# schematic.net
KiCad netlist of a schematic drawn in Altium Designer
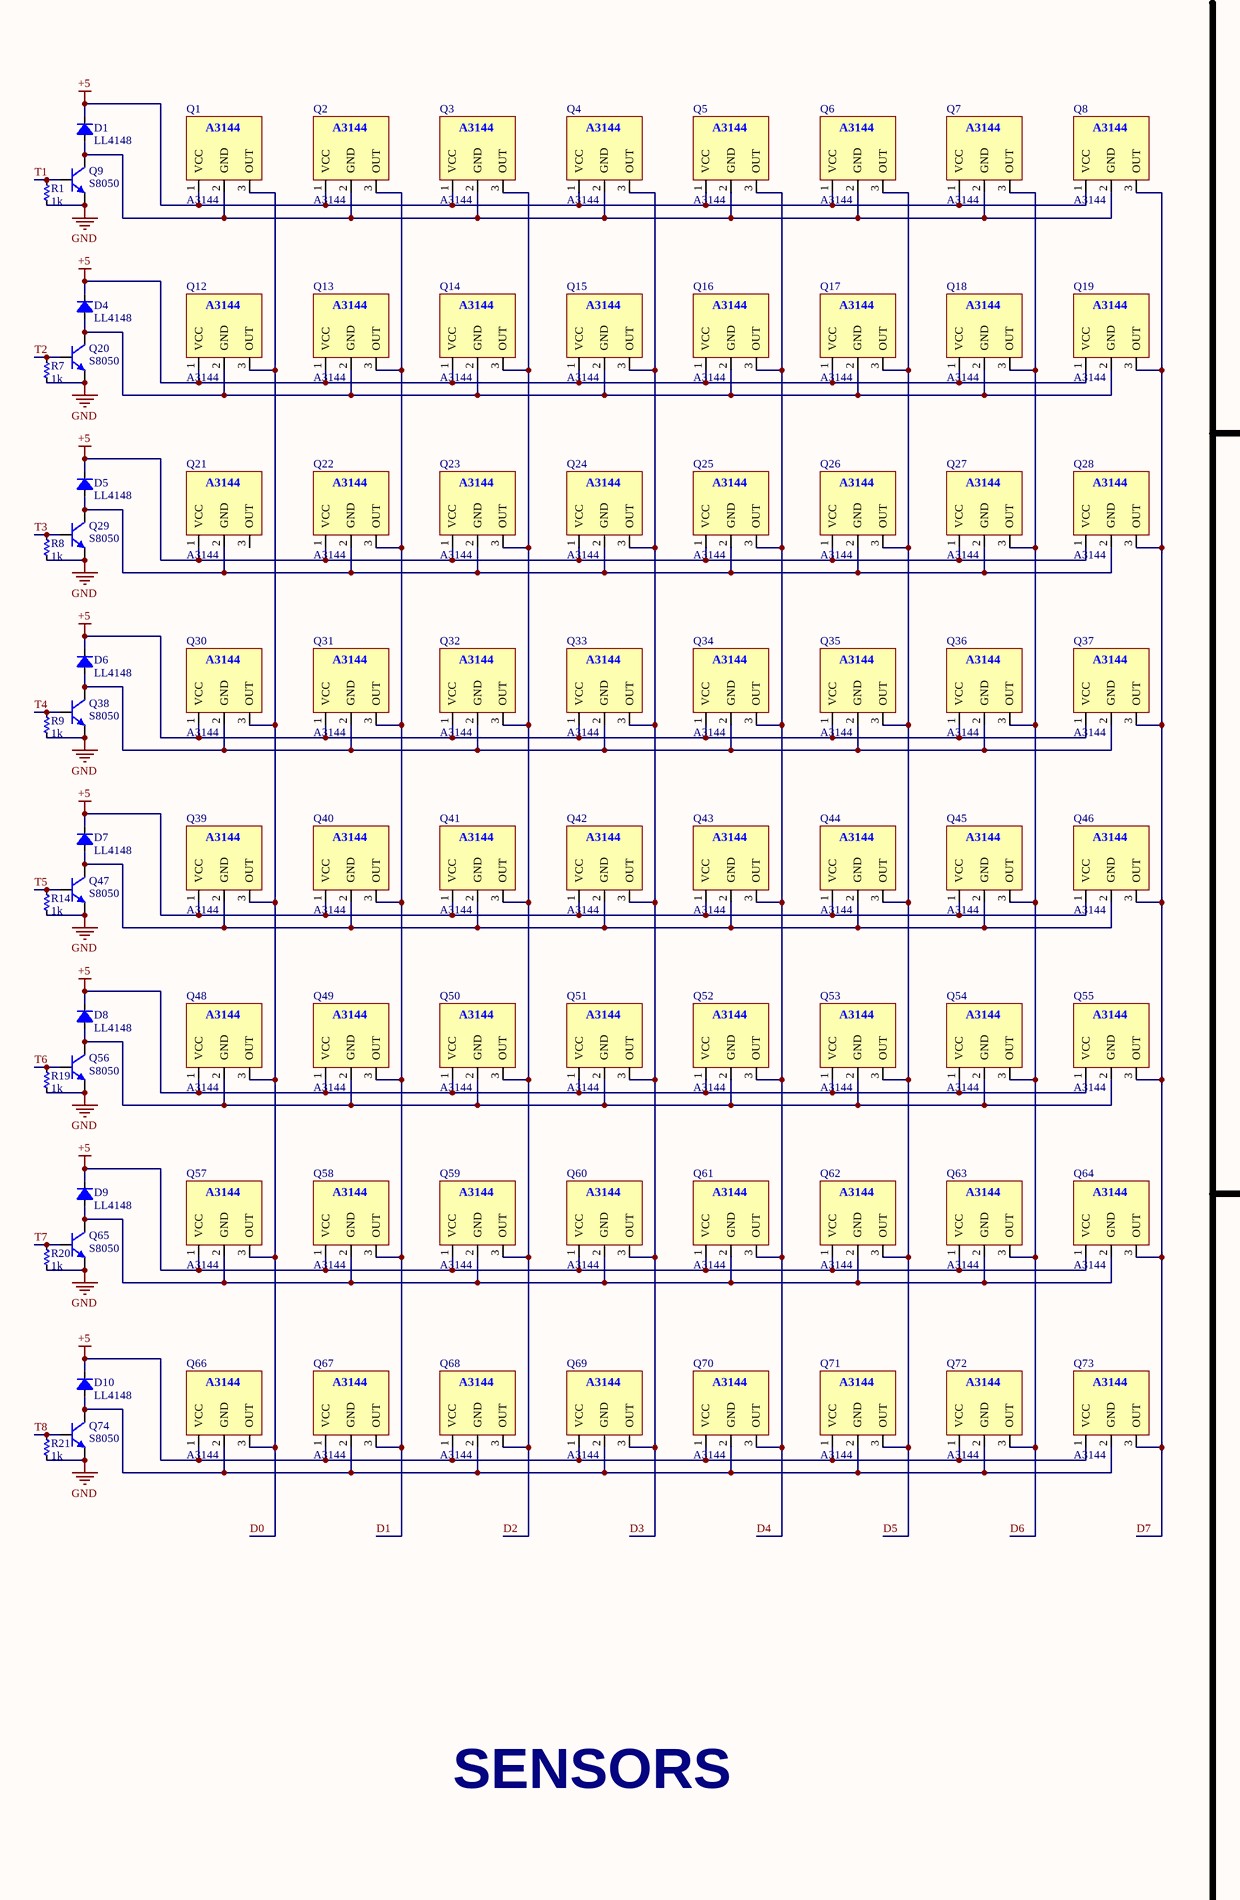
[diagram p0: schematic.SchDoc, left]
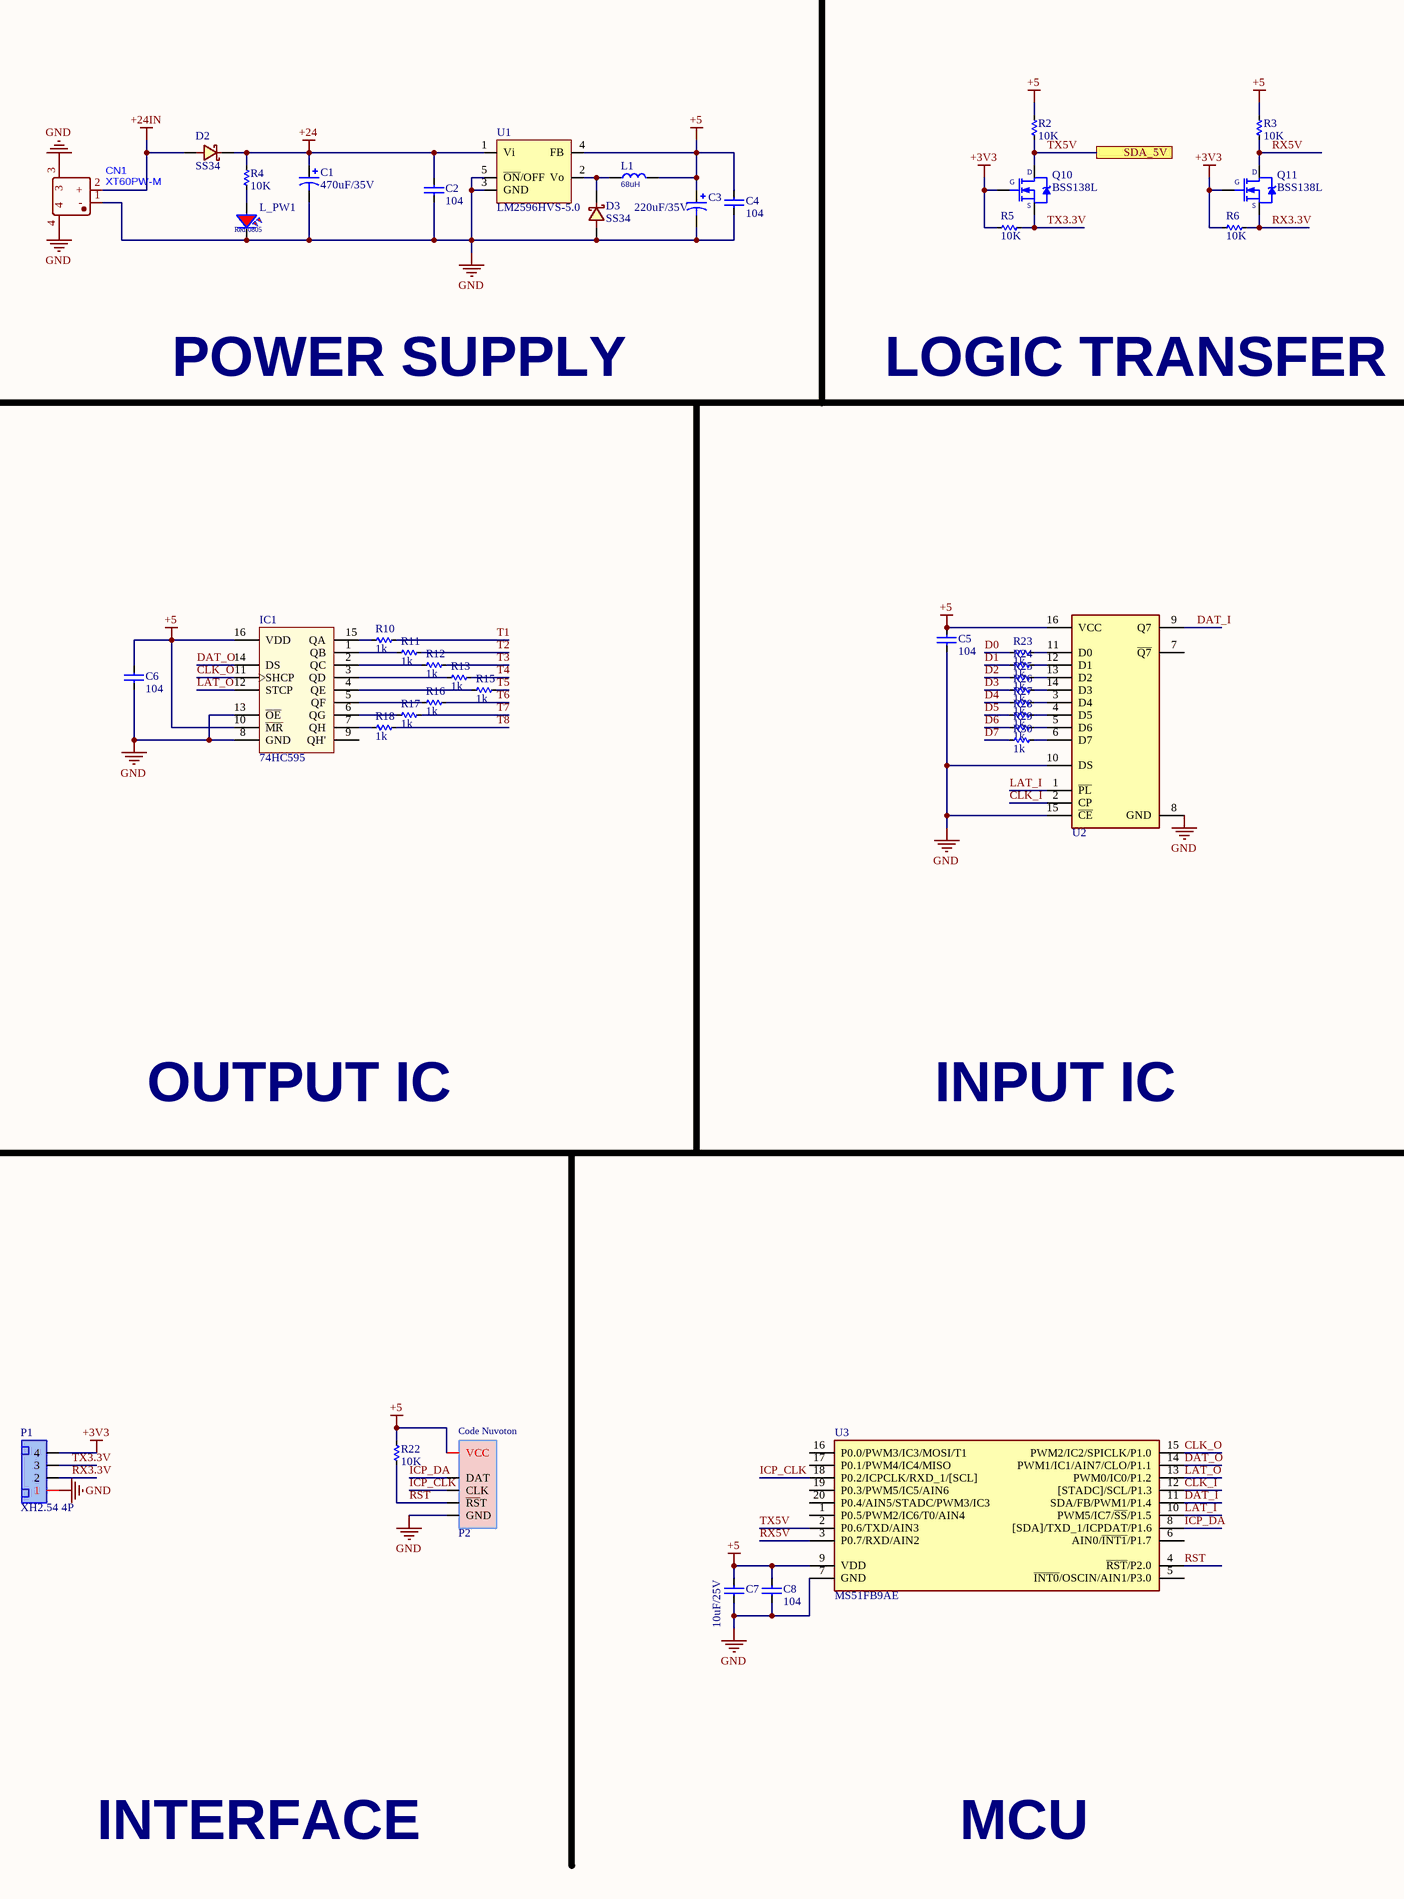
[diagram p1: schematic.SchDoc, right]

(export (version "E")
  (design (tool "Eeschema 10.0.6"))
  (components
    (comp (ref "C1")
      (value "470uF/35V")
      (footprint "C8X12mm")
      (description "Polarized Capacitor (Axial) 470uF 35V")
      (libsource (lib "RD Integrated_Library") (part "Cap Pol 470uF/35V"))
    )
    (comp (ref "C2")
      (value "104")
      (footprint "C_0805_SMD")
      (description "Cap SMD 0805 104-100nF-0.1uF 50V")
      (libsource (lib "RD Integrated_Library") (part "Cap 0805 104 100nF"))
    )
    (comp (ref "C3")
      (value "220uF/35V")
      (footprint "C8X12mm")
      (description "Polarized Capacitor (Axial) 220uF 35V")
      (libsource (lib "RD Integrated_Library") (part "Cap Pol 220uF/35V"))
    )
    (comp (ref "C4")
      (value "104")
      (footprint "C_0805_SMD")
      (description "Cap SMD 0805 104-100nF-0.1uF 50V")
      (libsource (lib "RD Integrated_Library") (part "Cap 0805 104 100nF"))
    )
    (comp (ref "C5")
      (value "104")
      (footprint "C_0805_SMD")
      (description "Cap SMD 0805 104-100nF-0.1uF 50V")
      (libsource (lib "RD Integrated_Library") (part "Cap 0805 104 100nF"))
    )
    (comp (ref "C6")
      (value "104")
      (footprint "C_0805_SMD")
      (description "Cap SMD 0805 104-100nF-0.1uF 50V")
      (libsource (lib "RD Integrated_Library") (part "Cap 0805 104 100nF"))
    )
    (comp (ref "C7")
      (value "10uF/25V")
      (footprint "C_0805_SMD")
      (description "Cap SMD 0805 10uF")
      (libsource (lib "RD Integrated_Library") (part "Cap 0805 10uF 25V"))
    )
    (comp (ref "C8")
      (value "104")
      (footprint "C_0805_SMD")
      (description "Cap SMD 0805 104-100nF-0.1uF 50V")
      (libsource (lib "RD Integrated_Library") (part "Cap 0805 104 100nF"))
    )
    (comp (ref "CN1")
      (value "XT60PW-M")
      (footprint "CONN-TH_XT60PW-M")
      (libsource (lib "Dlib") (part "XT60PW-M"))
    )
    (comp (ref "D1")
      (value "LL4148")
      (footprint "SOD80C_MFG")
      (description "0.2A, 100V, SOD80")
      (fields (field (name "DESIGNED BY") "Nhox"))
      (libsource (lib "RD Integrated_Library") (part "LL4148"))
    )
    (comp (ref "D2")
      (value "SS34")
      (footprint "D_SMA")
      (description "Surface-Mount Schottky Barrier Rectifier")
      (libsource (lib "RD Integrated_Library") (part "SS34-SMA"))
    )
    (comp (ref "D3")
      (value "SS34")
      (footprint "D_SMA")
      (description "Surface-Mount Schottky Barrier Rectifier")
      (libsource (lib "RD Integrated_Library") (part "SS34-SMA"))
    )
    (comp (ref "D4")
      (value "LL4148")
      (footprint "SOD80C_MFG")
      (description "0.2A, 100V, SOD80")
      (fields (field (name "DESIGNED BY") "Nhox"))
      (libsource (lib "RD Integrated_Library") (part "LL4148"))
    )
    (comp (ref "D5")
      (value "LL4148")
      (footprint "SOD80C_MFG")
      (description "0.2A, 100V, SOD80")
      (fields (field (name "DESIGNED BY") "Nhox"))
      (libsource (lib "RD Integrated_Library") (part "LL4148"))
    )
    (comp (ref "D6")
      (value "LL4148")
      (footprint "SOD80C_MFG")
      (description "0.2A, 100V, SOD80")
      (fields (field (name "DESIGNED BY") "Nhox"))
      (libsource (lib "RD Integrated_Library") (part "LL4148"))
    )
    (comp (ref "D7")
      (value "LL4148")
      (footprint "SOD80C_MFG")
      (description "0.2A, 100V, SOD80")
      (fields (field (name "DESIGNED BY") "Nhox"))
      (libsource (lib "RD Integrated_Library") (part "LL4148"))
    )
    (comp (ref "D8")
      (value "LL4148")
      (footprint "SOD80C_MFG")
      (description "0.2A, 100V, SOD80")
      (fields (field (name "DESIGNED BY") "Nhox"))
      (libsource (lib "RD Integrated_Library") (part "LL4148"))
    )
    (comp (ref "D9")
      (value "LL4148")
      (footprint "SOD80C_MFG")
      (description "0.2A, 100V, SOD80")
      (fields (field (name "DESIGNED BY") "Nhox"))
      (libsource (lib "RD Integrated_Library") (part "LL4148"))
    )
    (comp (ref "D10")
      (value "LL4148")
      (footprint "SOD80C_MFG")
      (description "0.2A, 100V, SOD80")
      (fields (field (name "DESIGNED BY") "Nhox"))
      (libsource (lib "RD Integrated_Library") (part "LL4148"))
    )
    (comp (ref "IC1")
      (value "74HC595")
      (footprint "SO_16")
      (description "Shift Register Single 8-Bit Serial to Serial/Parallel 16-Pin SOIC T/R")
      (fields (field (name "DESIGNED BY") "nhox"))
      (libsource (lib "RD Integrated_Library") (part "74HC595 SMD SO16"))
    )
    (comp (ref "L1")
      (value "68uH")
      (footprint "CDRH127")
      (description "CDRH127 Cuộn Cảm Dán SMD 1280-680 68uH 3.2A")
      (libsource (lib "RD Integrated_Library") (part "IND CDRH127 1280-680 68uH"))
    )
    (comp (ref "L_PW1")
      (value "LED RED")
      (footprint "LED 0805 Red")
      (description "LED 0805 SMD RED")
      (fields (field (name "DESIGNED BY") "TranLuyen"))
      (libsource (lib "RD Integrated_Library") (part "LED 0805 RED"))
    )
    (comp (ref "P1")
      (value "XH2.54 4P")
      (footprint "XH2.54_4P_RA")
      (description "XH2.54 RA")
      (libsource (lib "RD Integrated_Library") (part "XH2.54_4P_RA"))
    )
    (comp (ref "P2")
      (value "Nuvoton")
      (footprint "Header Code Nuvoton 2.54 6P")
      (description "Header 6-5Pin")
      (libsource (lib "RD Integrated_Library") (part "Header Code Nuvoton"))
    )
    (comp (ref "Q1")
      (value "A3144")
      (footprint "QTO-92")
      (description "Sensitive Hall Effect Switches for High-Temperature Operation 4.5-24V")
      (libsource (lib "RD Integrated_Library") (part "hall sensor A3144"))
    )
    (comp (ref "Q2")
      (value "A3144")
      (footprint "QTO-92")
      (description "Sensitive Hall Effect Switches for High-Temperature Operation 4.5-24V")
      (libsource (lib "RD Integrated_Library") (part "hall sensor A3144"))
    )
    (comp (ref "Q3")
      (value "A3144")
      (footprint "QTO-92")
      (description "Sensitive Hall Effect Switches for High-Temperature Operation 4.5-24V")
      (libsource (lib "RD Integrated_Library") (part "hall sensor A3144"))
    )
    (comp (ref "Q4")
      (value "A3144")
      (footprint "QTO-92")
      (description "Sensitive Hall Effect Switches for High-Temperature Operation 4.5-24V")
      (libsource (lib "RD Integrated_Library") (part "hall sensor A3144"))
    )
    (comp (ref "Q5")
      (value "A3144")
      (footprint "QTO-92")
      (description "Sensitive Hall Effect Switches for High-Temperature Operation 4.5-24V")
      (libsource (lib "RD Integrated_Library") (part "hall sensor A3144"))
    )
    (comp (ref "Q6")
      (value "A3144")
      (footprint "QTO-92")
      (description "Sensitive Hall Effect Switches for High-Temperature Operation 4.5-24V")
      (libsource (lib "RD Integrated_Library") (part "hall sensor A3144"))
    )
    (comp (ref "Q7")
      (value "A3144")
      (footprint "QTO-92")
      (description "Sensitive Hall Effect Switches for High-Temperature Operation 4.5-24V")
      (libsource (lib "RD Integrated_Library") (part "hall sensor A3144"))
    )
    (comp (ref "Q8")
      (value "A3144")
      (footprint "QTO-92")
      (description "Sensitive Hall Effect Switches for High-Temperature Operation 4.5-24V")
      (libsource (lib "RD Integrated_Library") (part "hall sensor A3144"))
    )
    (comp (ref "Q9")
      (value "S8050")
      (footprint "SOT23_N NXP")
      (description "J3Y-NPN SMD Transistor SOT23")
      (libsource (lib "RD Integrated_Library") (part "S8050 SOT-23"))
    )
    (comp (ref "Q10")
      (value "BSS138L")
      (footprint "SOT23_N NXP")
      (description "Power MOSFET 200 mA, 50V, N−Channel SOT23")
      (libsource (lib "RD Integrated_Library") (part "BSS138L SOT23"))
    )
    (comp (ref "Q11")
      (value "BSS138L")
      (footprint "SOT23_N NXP")
      (description "Power MOSFET 200 mA, 50V, N−Channel SOT23")
      (libsource (lib "RD Integrated_Library") (part "BSS138L SOT23"))
    )
    (comp (ref "Q12")
      (value "A3144")
      (footprint "QTO-92")
      (description "Sensitive Hall Effect Switches for High-Temperature Operation 4.5-24V")
      (libsource (lib "RD Integrated_Library") (part "hall sensor A3144"))
    )
    (comp (ref "Q13")
      (value "A3144")
      (footprint "QTO-92")
      (description "Sensitive Hall Effect Switches for High-Temperature Operation 4.5-24V")
      (libsource (lib "RD Integrated_Library") (part "hall sensor A3144"))
    )
    (comp (ref "Q14")
      (value "A3144")
      (footprint "QTO-92")
      (description "Sensitive Hall Effect Switches for High-Temperature Operation 4.5-24V")
      (libsource (lib "RD Integrated_Library") (part "hall sensor A3144"))
    )
    (comp (ref "Q15")
      (value "A3144")
      (footprint "QTO-92")
      (description "Sensitive Hall Effect Switches for High-Temperature Operation 4.5-24V")
      (libsource (lib "RD Integrated_Library") (part "hall sensor A3144"))
    )
    (comp (ref "Q16")
      (value "A3144")
      (footprint "QTO-92")
      (description "Sensitive Hall Effect Switches for High-Temperature Operation 4.5-24V")
      (libsource (lib "RD Integrated_Library") (part "hall sensor A3144"))
    )
    (comp (ref "Q17")
      (value "A3144")
      (footprint "QTO-92")
      (description "Sensitive Hall Effect Switches for High-Temperature Operation 4.5-24V")
      (libsource (lib "RD Integrated_Library") (part "hall sensor A3144"))
    )
    (comp (ref "Q18")
      (value "A3144")
      (footprint "QTO-92")
      (description "Sensitive Hall Effect Switches for High-Temperature Operation 4.5-24V")
      (libsource (lib "RD Integrated_Library") (part "hall sensor A3144"))
    )
    (comp (ref "Q19")
      (value "A3144")
      (footprint "QTO-92")
      (description "Sensitive Hall Effect Switches for High-Temperature Operation 4.5-24V")
      (libsource (lib "RD Integrated_Library") (part "hall sensor A3144"))
    )
    (comp (ref "Q20")
      (value "S8050")
      (footprint "SOT23_N NXP")
      (description "J3Y-NPN SMD Transistor SOT23")
      (libsource (lib "RD Integrated_Library") (part "S8050 SOT-23"))
    )
    (comp (ref "Q21")
      (value "A3144")
      (footprint "QTO-92")
      (description "Sensitive Hall Effect Switches for High-Temperature Operation 4.5-24V")
      (libsource (lib "RD Integrated_Library") (part "hall sensor A3144"))
    )
    (comp (ref "Q22")
      (value "A3144")
      (footprint "QTO-92")
      (description "Sensitive Hall Effect Switches for High-Temperature Operation 4.5-24V")
      (libsource (lib "RD Integrated_Library") (part "hall sensor A3144"))
    )
    (comp (ref "Q23")
      (value "A3144")
      (footprint "QTO-92")
      (description "Sensitive Hall Effect Switches for High-Temperature Operation 4.5-24V")
      (libsource (lib "RD Integrated_Library") (part "hall sensor A3144"))
    )
    (comp (ref "Q24")
      (value "A3144")
      (footprint "QTO-92")
      (description "Sensitive Hall Effect Switches for High-Temperature Operation 4.5-24V")
      (libsource (lib "RD Integrated_Library") (part "hall sensor A3144"))
    )
    (comp (ref "Q25")
      (value "A3144")
      (footprint "QTO-92")
      (description "Sensitive Hall Effect Switches for High-Temperature Operation 4.5-24V")
      (libsource (lib "RD Integrated_Library") (part "hall sensor A3144"))
    )
    (comp (ref "Q26")
      (value "A3144")
      (footprint "QTO-92")
      (description "Sensitive Hall Effect Switches for High-Temperature Operation 4.5-24V")
      (libsource (lib "RD Integrated_Library") (part "hall sensor A3144"))
    )
    (comp (ref "Q27")
      (value "A3144")
      (footprint "QTO-92")
      (description "Sensitive Hall Effect Switches for High-Temperature Operation 4.5-24V")
      (libsource (lib "RD Integrated_Library") (part "hall sensor A3144"))
    )
    (comp (ref "Q28")
      (value "A3144")
      (footprint "QTO-92")
      (description "Sensitive Hall Effect Switches for High-Temperature Operation 4.5-24V")
      (libsource (lib "RD Integrated_Library") (part "hall sensor A3144"))
    )
    (comp (ref "Q29")
      (value "S8050")
      (footprint "SOT23_N NXP")
      (description "J3Y-NPN SMD Transistor SOT23")
      (libsource (lib "RD Integrated_Library") (part "S8050 SOT-23"))
    )
    (comp (ref "Q30")
      (value "A3144")
      (footprint "QTO-92")
      (description "Sensitive Hall Effect Switches for High-Temperature Operation 4.5-24V")
      (libsource (lib "RD Integrated_Library") (part "hall sensor A3144"))
    )
    (comp (ref "Q31")
      (value "A3144")
      (footprint "QTO-92")
      (description "Sensitive Hall Effect Switches for High-Temperature Operation 4.5-24V")
      (libsource (lib "RD Integrated_Library") (part "hall sensor A3144"))
    )
    (comp (ref "Q32")
      (value "A3144")
      (footprint "QTO-92")
      (description "Sensitive Hall Effect Switches for High-Temperature Operation 4.5-24V")
      (libsource (lib "RD Integrated_Library") (part "hall sensor A3144"))
    )
    (comp (ref "Q33")
      (value "A3144")
      (footprint "QTO-92")
      (description "Sensitive Hall Effect Switches for High-Temperature Operation 4.5-24V")
      (libsource (lib "RD Integrated_Library") (part "hall sensor A3144"))
    )
    (comp (ref "Q34")
      (value "A3144")
      (footprint "QTO-92")
      (description "Sensitive Hall Effect Switches for High-Temperature Operation 4.5-24V")
      (libsource (lib "RD Integrated_Library") (part "hall sensor A3144"))
    )
    (comp (ref "Q35")
      (value "A3144")
      (footprint "QTO-92")
      (description "Sensitive Hall Effect Switches for High-Temperature Operation 4.5-24V")
      (libsource (lib "RD Integrated_Library") (part "hall sensor A3144"))
    )
    (comp (ref "Q36")
      (value "A3144")
      (footprint "QTO-92")
      (description "Sensitive Hall Effect Switches for High-Temperature Operation 4.5-24V")
      (libsource (lib "RD Integrated_Library") (part "hall sensor A3144"))
    )
    (comp (ref "Q37")
      (value "A3144")
      (footprint "QTO-92")
      (description "Sensitive Hall Effect Switches for High-Temperature Operation 4.5-24V")
      (libsource (lib "RD Integrated_Library") (part "hall sensor A3144"))
    )
    (comp (ref "Q38")
      (value "S8050")
      (footprint "SOT23_N NXP")
      (description "J3Y-NPN SMD Transistor SOT23")
      (libsource (lib "RD Integrated_Library") (part "S8050 SOT-23"))
    )
    (comp (ref "Q39")
      (value "A3144")
      (footprint "QTO-92")
      (description "Sensitive Hall Effect Switches for High-Temperature Operation 4.5-24V")
      (libsource (lib "RD Integrated_Library") (part "hall sensor A3144"))
    )
    (comp (ref "Q40")
      (value "A3144")
      (footprint "QTO-92")
      (description "Sensitive Hall Effect Switches for High-Temperature Operation 4.5-24V")
      (libsource (lib "RD Integrated_Library") (part "hall sensor A3144"))
    )
    (comp (ref "Q41")
      (value "A3144")
      (footprint "QTO-92")
      (description "Sensitive Hall Effect Switches for High-Temperature Operation 4.5-24V")
      (libsource (lib "RD Integrated_Library") (part "hall sensor A3144"))
    )
    (comp (ref "Q42")
      (value "A3144")
      (footprint "QTO-92")
      (description "Sensitive Hall Effect Switches for High-Temperature Operation 4.5-24V")
      (libsource (lib "RD Integrated_Library") (part "hall sensor A3144"))
    )
    (comp (ref "Q43")
      (value "A3144")
      (footprint "QTO-92")
      (description "Sensitive Hall Effect Switches for High-Temperature Operation 4.5-24V")
      (libsource (lib "RD Integrated_Library") (part "hall sensor A3144"))
    )
    (comp (ref "Q44")
      (value "A3144")
      (footprint "QTO-92")
      (description "Sensitive Hall Effect Switches for High-Temperature Operation 4.5-24V")
      (libsource (lib "RD Integrated_Library") (part "hall sensor A3144"))
    )
    (comp (ref "Q45")
      (value "A3144")
      (footprint "QTO-92")
      (description "Sensitive Hall Effect Switches for High-Temperature Operation 4.5-24V")
      (libsource (lib "RD Integrated_Library") (part "hall sensor A3144"))
    )
    (comp (ref "Q46")
      (value "A3144")
      (footprint "QTO-92")
      (description "Sensitive Hall Effect Switches for High-Temperature Operation 4.5-24V")
      (libsource (lib "RD Integrated_Library") (part "hall sensor A3144"))
    )
    (comp (ref "Q47")
      (value "S8050")
      (footprint "SOT23_N NXP")
      (description "J3Y-NPN SMD Transistor SOT23")
      (libsource (lib "RD Integrated_Library") (part "S8050 SOT-23"))
    )
    (comp (ref "Q48")
      (value "A3144")
      (footprint "QTO-92")
      (description "Sensitive Hall Effect Switches for High-Temperature Operation 4.5-24V")
      (libsource (lib "RD Integrated_Library") (part "hall sensor A3144"))
    )
    (comp (ref "Q49")
      (value "A3144")
      (footprint "QTO-92")
      (description "Sensitive Hall Effect Switches for High-Temperature Operation 4.5-24V")
      (libsource (lib "RD Integrated_Library") (part "hall sensor A3144"))
    )
    (comp (ref "Q50")
      (value "A3144")
      (footprint "QTO-92")
      (description "Sensitive Hall Effect Switches for High-Temperature Operation 4.5-24V")
      (libsource (lib "RD Integrated_Library") (part "hall sensor A3144"))
    )
    (comp (ref "Q51")
      (value "A3144")
      (footprint "QTO-92")
      (description "Sensitive Hall Effect Switches for High-Temperature Operation 4.5-24V")
      (libsource (lib "RD Integrated_Library") (part "hall sensor A3144"))
    )
    (comp (ref "Q52")
      (value "A3144")
      (footprint "QTO-92")
      (description "Sensitive Hall Effect Switches for High-Temperature Operation 4.5-24V")
      (libsource (lib "RD Integrated_Library") (part "hall sensor A3144"))
    )
    (comp (ref "Q53")
      (value "A3144")
      (footprint "QTO-92")
      (description "Sensitive Hall Effect Switches for High-Temperature Operation 4.5-24V")
      (libsource (lib "RD Integrated_Library") (part "hall sensor A3144"))
    )
    (comp (ref "Q54")
      (value "A3144")
      (footprint "QTO-92")
      (description "Sensitive Hall Effect Switches for High-Temperature Operation 4.5-24V")
      (libsource (lib "RD Integrated_Library") (part "hall sensor A3144"))
    )
    (comp (ref "Q55")
      (value "A3144")
      (footprint "QTO-92")
      (description "Sensitive Hall Effect Switches for High-Temperature Operation 4.5-24V")
      (libsource (lib "RD Integrated_Library") (part "hall sensor A3144"))
    )
    (comp (ref "Q56")
      (value "S8050")
      (footprint "SOT23_N NXP")
      (description "J3Y-NPN SMD Transistor SOT23")
      (libsource (lib "RD Integrated_Library") (part "S8050 SOT-23"))
    )
    (comp (ref "Q57")
      (value "A3144")
      (footprint "QTO-92")
      (description "Sensitive Hall Effect Switches for High-Temperature Operation 4.5-24V")
      (libsource (lib "RD Integrated_Library") (part "hall sensor A3144"))
    )
    (comp (ref "Q58")
      (value "A3144")
      (footprint "QTO-92")
      (description "Sensitive Hall Effect Switches for High-Temperature Operation 4.5-24V")
      (libsource (lib "RD Integrated_Library") (part "hall sensor A3144"))
    )
    (comp (ref "Q59")
      (value "A3144")
      (footprint "QTO-92")
      (description "Sensitive Hall Effect Switches for High-Temperature Operation 4.5-24V")
      (libsource (lib "RD Integrated_Library") (part "hall sensor A3144"))
    )
    (comp (ref "Q60")
      (value "A3144")
      (footprint "QTO-92")
      (description "Sensitive Hall Effect Switches for High-Temperature Operation 4.5-24V")
      (libsource (lib "RD Integrated_Library") (part "hall sensor A3144"))
    )
    (comp (ref "Q61")
      (value "A3144")
      (footprint "QTO-92")
      (description "Sensitive Hall Effect Switches for High-Temperature Operation 4.5-24V")
      (libsource (lib "RD Integrated_Library") (part "hall sensor A3144"))
    )
    (comp (ref "Q62")
      (value "A3144")
      (footprint "QTO-92")
      (description "Sensitive Hall Effect Switches for High-Temperature Operation 4.5-24V")
      (libsource (lib "RD Integrated_Library") (part "hall sensor A3144"))
    )
    (comp (ref "Q63")
      (value "A3144")
      (footprint "QTO-92")
      (description "Sensitive Hall Effect Switches for High-Temperature Operation 4.5-24V")
      (libsource (lib "RD Integrated_Library") (part "hall sensor A3144"))
    )
    (comp (ref "Q64")
      (value "A3144")
      (footprint "QTO-92")
      (description "Sensitive Hall Effect Switches for High-Temperature Operation 4.5-24V")
      (libsource (lib "RD Integrated_Library") (part "hall sensor A3144"))
    )
    (comp (ref "Q65")
      (value "S8050")
      (footprint "SOT23_N NXP")
      (description "J3Y-NPN SMD Transistor SOT23")
      (libsource (lib "RD Integrated_Library") (part "S8050 SOT-23"))
    )
    (comp (ref "Q66")
      (value "A3144")
      (footprint "QTO-92")
      (description "Sensitive Hall Effect Switches for High-Temperature Operation 4.5-24V")
      (libsource (lib "RD Integrated_Library") (part "hall sensor A3144"))
    )
    (comp (ref "Q67")
      (value "A3144")
      (footprint "QTO-92")
      (description "Sensitive Hall Effect Switches for High-Temperature Operation 4.5-24V")
      (libsource (lib "RD Integrated_Library") (part "hall sensor A3144"))
    )
    (comp (ref "Q68")
      (value "A3144")
      (footprint "QTO-92")
      (description "Sensitive Hall Effect Switches for High-Temperature Operation 4.5-24V")
      (libsource (lib "RD Integrated_Library") (part "hall sensor A3144"))
    )
    (comp (ref "Q69")
      (value "A3144")
      (footprint "QTO-92")
      (description "Sensitive Hall Effect Switches for High-Temperature Operation 4.5-24V")
      (libsource (lib "RD Integrated_Library") (part "hall sensor A3144"))
    )
    (comp (ref "Q70")
      (value "A3144")
      (footprint "QTO-92")
      (description "Sensitive Hall Effect Switches for High-Temperature Operation 4.5-24V")
      (libsource (lib "RD Integrated_Library") (part "hall sensor A3144"))
    )
    (comp (ref "Q71")
      (value "A3144")
      (footprint "QTO-92")
      (description "Sensitive Hall Effect Switches for High-Temperature Operation 4.5-24V")
      (libsource (lib "RD Integrated_Library") (part "hall sensor A3144"))
    )
    (comp (ref "Q72")
      (value "A3144")
      (footprint "QTO-92")
      (description "Sensitive Hall Effect Switches for High-Temperature Operation 4.5-24V")
      (libsource (lib "RD Integrated_Library") (part "hall sensor A3144"))
    )
    (comp (ref "Q73")
      (value "A3144")
      (footprint "QTO-92")
      (description "Sensitive Hall Effect Switches for High-Temperature Operation 4.5-24V")
      (libsource (lib "RD Integrated_Library") (part "hall sensor A3144"))
    )
    (comp (ref "Q74")
      (value "S8050")
      (footprint "SOT23_N NXP")
      (description "J3Y-NPN SMD Transistor SOT23")
      (libsource (lib "RD Integrated_Library") (part "S8050 SOT-23"))
    )
    (comp (ref "R1")
      (value "1k")
      (footprint "RES-SMD-0805")
      (description "Resistor SMD 0805")
      (libsource (lib "RD Integrated_Library") (part "Res 1k 0805"))
    )
    (comp (ref "R2")
      (value "10K")
      (footprint "RES-SMD-0805")
      (description "Resistor SMD 0805")
      (libsource (lib "RD Integrated_Library") (part "Res 10k 0805"))
    )
    (comp (ref "R3")
      (value "10K")
      (footprint "RES-SMD-0805")
      (description "Resistor SMD 0805")
      (libsource (lib "RD Integrated_Library") (part "Res 10k 0805"))
    )
    (comp (ref "R4")
      (value "10K")
      (footprint "RES-SMD-0805")
      (description "Resistor SMD 0805")
      (libsource (lib "RD Integrated_Library") (part "Res 10k 0805"))
    )
    (comp (ref "R5")
      (value "10K")
      (footprint "RES-SMD-0805")
      (description "Resistor SMD 0805")
      (libsource (lib "RD Integrated_Library") (part "Res 10k 0805"))
    )
    (comp (ref "R6")
      (value "10K")
      (footprint "RES-SMD-0805")
      (description "Resistor SMD 0805")
      (libsource (lib "RD Integrated_Library") (part "Res 10k 0805"))
    )
    (comp (ref "R7")
      (value "1k")
      (footprint "RES-SMD-0805")
      (description "Resistor SMD 0805")
      (libsource (lib "RD Integrated_Library") (part "Res 1k 0805"))
    )
    (comp (ref "R8")
      (value "1k")
      (footprint "RES-SMD-0805")
      (description "Resistor SMD 0805")
      (libsource (lib "RD Integrated_Library") (part "Res 1k 0805"))
    )
    (comp (ref "R9")
      (value "1k")
      (footprint "RES-SMD-0805")
      (description "Resistor SMD 0805")
      (libsource (lib "RD Integrated_Library") (part "Res 1k 0805"))
    )
    (comp (ref "R10")
      (value "1k")
      (footprint "RES-SMD-0805")
      (description "Resistor SMD 0805")
      (libsource (lib "RD Integrated_Library") (part "Res 1k 0805"))
    )
    (comp (ref "R11")
      (value "1k")
      (footprint "RES-SMD-0805")
      (description "Resistor SMD 0805")
      (libsource (lib "RD Integrated_Library") (part "Res 1k 0805"))
    )
    (comp (ref "R12")
      (value "1k")
      (footprint "RES-SMD-0805")
      (description "Resistor SMD 0805")
      (libsource (lib "RD Integrated_Library") (part "Res 1k 0805"))
    )
    (comp (ref "R13")
      (value "1k")
      (footprint "RES-SMD-0805")
      (description "Resistor SMD 0805")
      (libsource (lib "RD Integrated_Library") (part "Res 1k 0805"))
    )
    (comp (ref "R14")
      (value "1k")
      (footprint "RES-SMD-0805")
      (description "Resistor SMD 0805")
      (libsource (lib "RD Integrated_Library") (part "Res 1k 0805"))
    )
    (comp (ref "R15")
      (value "1k")
      (footprint "RES-SMD-0805")
      (description "Resistor SMD 0805")
      (libsource (lib "RD Integrated_Library") (part "Res 1k 0805"))
    )
    (comp (ref "R16")
      (value "1k")
      (footprint "RES-SMD-0805")
      (description "Resistor SMD 0805")
      (libsource (lib "RD Integrated_Library") (part "Res 1k 0805"))
    )
    (comp (ref "R17")
      (value "1k")
      (footprint "RES-SMD-0805")
      (description "Resistor SMD 0805")
      (libsource (lib "RD Integrated_Library") (part "Res 1k 0805"))
    )
    (comp (ref "R18")
      (value "1k")
      (footprint "RES-SMD-0805")
      (description "Resistor SMD 0805")
      (libsource (lib "RD Integrated_Library") (part "Res 1k 0805"))
    )
    (comp (ref "R19")
      (value "1k")
      (footprint "RES-SMD-0805")
      (description "Resistor SMD 0805")
      (libsource (lib "RD Integrated_Library") (part "Res 1k 0805"))
    )
    (comp (ref "R20")
      (value "1k")
      (footprint "RES-SMD-0805")
      (description "Resistor SMD 0805")
      (libsource (lib "RD Integrated_Library") (part "Res 1k 0805"))
    )
    (comp (ref "R21")
      (value "1k")
      (footprint "RES-SMD-0805")
      (description "Resistor SMD 0805")
      (libsource (lib "RD Integrated_Library") (part "Res 1k 0805"))
    )
    (comp (ref "R22")
      (value "10K")
      (footprint "RES-SMD-0805")
      (description "Resistor SMD 0805")
      (libsource (lib "RD Integrated_Library") (part "Res 10k 0805"))
    )
    (comp (ref "R23")
      (value "1k")
      (footprint "RES-SMD-0805")
      (description "Resistor SMD 0805")
      (libsource (lib "RD Integrated_Library") (part "Res 1k 0805"))
    )
    (comp (ref "R24")
      (value "1k")
      (footprint "RES-SMD-0805")
      (description "Resistor SMD 0805")
      (libsource (lib "RD Integrated_Library") (part "Res 1k 0805"))
    )
    (comp (ref "R25")
      (value "1k")
      (footprint "RES-SMD-0805")
      (description "Resistor SMD 0805")
      (libsource (lib "RD Integrated_Library") (part "Res 1k 0805"))
    )
    (comp (ref "R26")
      (value "1k")
      (footprint "RES-SMD-0805")
      (description "Resistor SMD 0805")
      (libsource (lib "RD Integrated_Library") (part "Res 1k 0805"))
    )
    (comp (ref "R27")
      (value "1k")
      (footprint "RES-SMD-0805")
      (description "Resistor SMD 0805")
      (libsource (lib "RD Integrated_Library") (part "Res 1k 0805"))
    )
    (comp (ref "R28")
      (value "1k")
      (footprint "RES-SMD-0805")
      (description "Resistor SMD 0805")
      (libsource (lib "RD Integrated_Library") (part "Res 1k 0805"))
    )
    (comp (ref "R29")
      (value "1k")
      (footprint "RES-SMD-0805")
      (description "Resistor SMD 0805")
      (libsource (lib "RD Integrated_Library") (part "Res 1k 0805"))
    )
    (comp (ref "R30")
      (value "1k")
      (footprint "RES-SMD-0805")
      (description "Resistor SMD 0805")
      (libsource (lib "RD Integrated_Library") (part "Res 1k 0805"))
    )
    (comp (ref "U1")
      (value "LM2596HVS-5.0")
      (footprint "TO-263-5")
      (description "Vin 4.5-40VDC, Vout 5VDC, Iout MAX 3A")
      (libsource (lib "RD Integrated_Library") (part "LM2596HVS-5.0"))
    )
    (comp (ref "U2")
      (value "74HC165")
      (footprint "SO_16")
      (description "IC Shift Register 1 Element 8 Bit, Complementary 16-SOIC")
      (fields (field (name "DESIGNED BY") "nhox"))
      (libsource (lib "RD Integrated_Library") (part "74HC165-SOIC-16"))
    )
    (comp (ref "U3")
      (value "MS51FB9AE")
      (footprint "SOG65_20")
      (description "MS51FB9AE, ROM 16KB, RAM 256B + 1KB, SPROM 128B, 1T 8051-based CMOS up to 24Mhz")
      (fields (field (name "DESIGNED BY") "Nhox"))
      (libsource (lib "RD Integrated_Library") (part "MS51FB9AE"))
    )
  )
  (nets
    (net (code "1") (name "+3V3") (class "Default")
      (node (ref "P1") (pin "4") (pinfunction "4_4") (pintype "passive"))
      (node (ref "Q10") (pin "1") (pinfunction "G_1") (pintype "passive"))
      (node (ref "Q11") (pin "1") (pinfunction "G_1") (pintype "passive"))
      (node (ref "R5") (pin "2") (pinfunction "2_2") (pintype "passive"))
      (node (ref "R6") (pin "2") (pinfunction "2_2") (pintype "passive"))
    )
    (net (code "2") (name "+5") (class "Default")
      (node (ref "C3") (pin "1") (pinfunction "1_1") (pintype "passive"))
      (node (ref "C4") (pin "2") (pinfunction "2_2") (pintype "passive"))
      (node (ref "C5") (pin "2") (pinfunction "2_2") (pintype "passive"))
      (node (ref "C6") (pin "2") (pinfunction "2_2") (pintype "passive"))
      (node (ref "C7") (pin "1") (pinfunction "1_1") (pintype "passive"))
      (node (ref "C8") (pin "1") (pinfunction "1_1") (pintype "passive"))
      (node (ref "D1") (pin "1") (pinfunction "1_1") (pintype "passive"))
      (node (ref "D10") (pin "1") (pinfunction "1_1") (pintype "passive"))
      (node (ref "D4") (pin "1") (pinfunction "1_1") (pintype "passive"))
      (node (ref "D5") (pin "1") (pinfunction "1_1") (pintype "passive"))
      (node (ref "D6") (pin "1") (pinfunction "1_1") (pintype "passive"))
      (node (ref "D7") (pin "1") (pinfunction "1_1") (pintype "passive"))
      (node (ref "D8") (pin "1") (pinfunction "1_1") (pintype "passive"))
      (node (ref "D9") (pin "1") (pinfunction "1_1") (pintype "passive"))
      (node (ref "IC1") (pin "10") (pinfunction "~{MR}_10") (pintype "passive"))
      (node (ref "IC1") (pin "16") (pinfunction "VDD_16") (pintype "power_in"))
      (node (ref "L1") (pin "2") (pinfunction "2_2") (pintype "passive"))
      (node (ref "P2") (pin "1") (pinfunction "VCC_1") (pintype "passive"))
      (node (ref "Q1") (pin "1") (pinfunction "VCC_1") (pintype "passive"))
      (node (ref "Q12") (pin "1") (pinfunction "VCC_1") (pintype "passive"))
      (node (ref "Q13") (pin "1") (pinfunction "VCC_1") (pintype "passive"))
      (node (ref "Q14") (pin "1") (pinfunction "VCC_1") (pintype "passive"))
      (node (ref "Q15") (pin "1") (pinfunction "VCC_1") (pintype "passive"))
      (node (ref "Q16") (pin "1") (pinfunction "VCC_1") (pintype "passive"))
      (node (ref "Q17") (pin "1") (pinfunction "VCC_1") (pintype "passive"))
      (node (ref "Q18") (pin "1") (pinfunction "VCC_1") (pintype "passive"))
      (node (ref "Q19") (pin "1") (pinfunction "VCC_1") (pintype "passive"))
      (node (ref "Q2") (pin "1") (pinfunction "VCC_1") (pintype "passive"))
      (node (ref "Q21") (pin "1") (pinfunction "VCC_1") (pintype "passive"))
      (node (ref "Q22") (pin "1") (pinfunction "VCC_1") (pintype "passive"))
      (node (ref "Q23") (pin "1") (pinfunction "VCC_1") (pintype "passive"))
      (node (ref "Q24") (pin "1") (pinfunction "VCC_1") (pintype "passive"))
      (node (ref "Q25") (pin "1") (pinfunction "VCC_1") (pintype "passive"))
      (node (ref "Q26") (pin "1") (pinfunction "VCC_1") (pintype "passive"))
      (node (ref "Q27") (pin "1") (pinfunction "VCC_1") (pintype "passive"))
      (node (ref "Q28") (pin "1") (pinfunction "VCC_1") (pintype "passive"))
      (node (ref "Q3") (pin "1") (pinfunction "VCC_1") (pintype "passive"))
      (node (ref "Q30") (pin "1") (pinfunction "VCC_1") (pintype "passive"))
      (node (ref "Q31") (pin "1") (pinfunction "VCC_1") (pintype "passive"))
      (node (ref "Q32") (pin "1") (pinfunction "VCC_1") (pintype "passive"))
      (node (ref "Q33") (pin "1") (pinfunction "VCC_1") (pintype "passive"))
      (node (ref "Q34") (pin "1") (pinfunction "VCC_1") (pintype "passive"))
      (node (ref "Q35") (pin "1") (pinfunction "VCC_1") (pintype "passive"))
      (node (ref "Q36") (pin "1") (pinfunction "VCC_1") (pintype "passive"))
      (node (ref "Q37") (pin "1") (pinfunction "VCC_1") (pintype "passive"))
      (node (ref "Q39") (pin "1") (pinfunction "VCC_1") (pintype "passive"))
      (node (ref "Q4") (pin "1") (pinfunction "VCC_1") (pintype "passive"))
      (node (ref "Q40") (pin "1") (pinfunction "VCC_1") (pintype "passive"))
      (node (ref "Q41") (pin "1") (pinfunction "VCC_1") (pintype "passive"))
      (node (ref "Q42") (pin "1") (pinfunction "VCC_1") (pintype "passive"))
      (node (ref "Q43") (pin "1") (pinfunction "VCC_1") (pintype "passive"))
      (node (ref "Q44") (pin "1") (pinfunction "VCC_1") (pintype "passive"))
      (node (ref "Q45") (pin "1") (pinfunction "VCC_1") (pintype "passive"))
      (node (ref "Q46") (pin "1") (pinfunction "VCC_1") (pintype "passive"))
      (node (ref "Q48") (pin "1") (pinfunction "VCC_1") (pintype "passive"))
      (node (ref "Q49") (pin "1") (pinfunction "VCC_1") (pintype "passive"))
      (node (ref "Q5") (pin "1") (pinfunction "VCC_1") (pintype "passive"))
      (node (ref "Q50") (pin "1") (pinfunction "VCC_1") (pintype "passive"))
      (node (ref "Q51") (pin "1") (pinfunction "VCC_1") (pintype "passive"))
      (node (ref "Q52") (pin "1") (pinfunction "VCC_1") (pintype "passive"))
      (node (ref "Q53") (pin "1") (pinfunction "VCC_1") (pintype "passive"))
      (node (ref "Q54") (pin "1") (pinfunction "VCC_1") (pintype "passive"))
      (node (ref "Q55") (pin "1") (pinfunction "VCC_1") (pintype "passive"))
      (node (ref "Q57") (pin "1") (pinfunction "VCC_1") (pintype "passive"))
      (node (ref "Q58") (pin "1") (pinfunction "VCC_1") (pintype "passive"))
      (node (ref "Q59") (pin "1") (pinfunction "VCC_1") (pintype "passive"))
      (node (ref "Q6") (pin "1") (pinfunction "VCC_1") (pintype "passive"))
      (node (ref "Q60") (pin "1") (pinfunction "VCC_1") (pintype "passive"))
      (node (ref "Q61") (pin "1") (pinfunction "VCC_1") (pintype "passive"))
      (node (ref "Q62") (pin "1") (pinfunction "VCC_1") (pintype "passive"))
      (node (ref "Q63") (pin "1") (pinfunction "VCC_1") (pintype "passive"))
      (node (ref "Q64") (pin "1") (pinfunction "VCC_1") (pintype "passive"))
      (node (ref "Q66") (pin "1") (pinfunction "VCC_1") (pintype "passive"))
      (node (ref "Q67") (pin "1") (pinfunction "VCC_1") (pintype "passive"))
      (node (ref "Q68") (pin "1") (pinfunction "VCC_1") (pintype "passive"))
      (node (ref "Q69") (pin "1") (pinfunction "VCC_1") (pintype "passive"))
      (node (ref "Q7") (pin "1") (pinfunction "VCC_1") (pintype "passive"))
      (node (ref "Q70") (pin "1") (pinfunction "VCC_1") (pintype "passive"))
      (node (ref "Q71") (pin "1") (pinfunction "VCC_1") (pintype "passive"))
      (node (ref "Q72") (pin "1") (pinfunction "VCC_1") (pintype "passive"))
      (node (ref "Q73") (pin "1") (pinfunction "VCC_1") (pintype "passive"))
      (node (ref "Q8") (pin "1") (pinfunction "VCC_1") (pintype "passive"))
      (node (ref "R2") (pin "2") (pinfunction "2_2") (pintype "passive"))
      (node (ref "R22") (pin "1") (pinfunction "1_1") (pintype "passive"))
      (node (ref "R3") (pin "2") (pinfunction "2_2") (pintype "passive"))
      (node (ref "U1") (pin "4") (pinfunction "FB_4") (pintype "passive"))
      (node (ref "U2") (pin "16") (pinfunction "VCC_16") (pintype "power_in"))
      (node (ref "U3") (pin "9") (pinfunction "VDD_9") (pintype "passive"))
    )
    (net (code "3") (name "+24") (class "Default")
      (node (ref "C1") (pin "1") (pinfunction "1_1") (pintype "passive"))
      (node (ref "C2") (pin "2") (pinfunction "2_2") (pintype "passive"))
      (node (ref "D2") (pin "2") (pinfunction "K_2") (pintype "passive"))
      (node (ref "R4") (pin "1") (pinfunction "1_1") (pintype "passive"))
      (node (ref "U1") (pin "1") (pinfunction "Vi_1") (pintype "passive"))
    )
    (net (code "4") (name "+24IN") (class "Default")
      (node (ref "CN1") (pin "2") (pinfunction "+_2") (pintype "passive"))
      (node (ref "D2") (pin "1") (pinfunction "A_1") (pintype "passive"))
    )
    (net (code "5") (name "/CLK_I") (class "Default")
      (node (ref "U2") (pin "2") (pinfunction "CP_2") (pintype "passive"))
      (node (ref "U3") (pin "12") (pinfunction "[STADC]/SCL/P1.3_12") (pintype "passive"))
    )
    (net (code "6") (name "/CLK_O") (class "Default")
      (node (ref "IC1") (pin "11") (pinfunction "SHCP_11") (pintype "passive"))
      (node (ref "U3") (pin "15") (pinfunction "PWM2/IC2/SPICLK/P1.0_15") (pintype "passive"))
    )
    (net (code "7") (name "/D0") (class "Default")
      (node (ref "Q1") (pin "3") (pinfunction "OUT_3") (pintype "passive"))
      (node (ref "Q12") (pin "3") (pinfunction "OUT_3") (pintype "passive"))
      (node (ref "Q30") (pin "3") (pinfunction "OUT_3") (pintype "passive"))
      (node (ref "Q39") (pin "3") (pinfunction "OUT_3") (pintype "passive"))
      (node (ref "Q48") (pin "3") (pinfunction "OUT_3") (pintype "passive"))
      (node (ref "Q57") (pin "3") (pinfunction "OUT_3") (pintype "passive"))
      (node (ref "Q66") (pin "3") (pinfunction "OUT_3") (pintype "passive"))
      (node (ref "R23") (pin "2") (pinfunction "2_2") (pintype "passive"))
    )
    (net (code "8") (name "/D1") (class "Default")
      (node (ref "Q13") (pin "3") (pinfunction "OUT_3") (pintype "passive"))
      (node (ref "Q2") (pin "3") (pinfunction "OUT_3") (pintype "passive"))
      (node (ref "Q22") (pin "3") (pinfunction "OUT_3") (pintype "passive"))
      (node (ref "Q31") (pin "3") (pinfunction "OUT_3") (pintype "passive"))
      (node (ref "Q40") (pin "3") (pinfunction "OUT_3") (pintype "passive"))
      (node (ref "Q49") (pin "3") (pinfunction "OUT_3") (pintype "passive"))
      (node (ref "Q58") (pin "3") (pinfunction "OUT_3") (pintype "passive"))
      (node (ref "Q67") (pin "3") (pinfunction "OUT_3") (pintype "passive"))
      (node (ref "R24") (pin "2") (pinfunction "2_2") (pintype "passive"))
    )
    (net (code "9") (name "/D2") (class "Default")
      (node (ref "Q14") (pin "3") (pinfunction "OUT_3") (pintype "passive"))
      (node (ref "Q23") (pin "3") (pinfunction "OUT_3") (pintype "passive"))
      (node (ref "Q3") (pin "3") (pinfunction "OUT_3") (pintype "passive"))
      (node (ref "Q32") (pin "3") (pinfunction "OUT_3") (pintype "passive"))
      (node (ref "Q41") (pin "3") (pinfunction "OUT_3") (pintype "passive"))
      (node (ref "Q50") (pin "3") (pinfunction "OUT_3") (pintype "passive"))
      (node (ref "Q59") (pin "3") (pinfunction "OUT_3") (pintype "passive"))
      (node (ref "Q68") (pin "3") (pinfunction "OUT_3") (pintype "passive"))
      (node (ref "R25") (pin "2") (pinfunction "2_2") (pintype "passive"))
    )
    (net (code "10") (name "/D3") (class "Default")
      (node (ref "Q15") (pin "3") (pinfunction "OUT_3") (pintype "passive"))
      (node (ref "Q24") (pin "3") (pinfunction "OUT_3") (pintype "passive"))
      (node (ref "Q33") (pin "3") (pinfunction "OUT_3") (pintype "passive"))
      (node (ref "Q4") (pin "3") (pinfunction "OUT_3") (pintype "passive"))
      (node (ref "Q42") (pin "3") (pinfunction "OUT_3") (pintype "passive"))
      (node (ref "Q51") (pin "3") (pinfunction "OUT_3") (pintype "passive"))
      (node (ref "Q60") (pin "3") (pinfunction "OUT_3") (pintype "passive"))
      (node (ref "Q69") (pin "3") (pinfunction "OUT_3") (pintype "passive"))
      (node (ref "R26") (pin "2") (pinfunction "2_2") (pintype "passive"))
    )
    (net (code "11") (name "/D4") (class "Default")
      (node (ref "Q16") (pin "3") (pinfunction "OUT_3") (pintype "passive"))
      (node (ref "Q25") (pin "3") (pinfunction "OUT_3") (pintype "passive"))
      (node (ref "Q34") (pin "3") (pinfunction "OUT_3") (pintype "passive"))
      (node (ref "Q43") (pin "3") (pinfunction "OUT_3") (pintype "passive"))
      (node (ref "Q5") (pin "3") (pinfunction "OUT_3") (pintype "passive"))
      (node (ref "Q52") (pin "3") (pinfunction "OUT_3") (pintype "passive"))
      (node (ref "Q61") (pin "3") (pinfunction "OUT_3") (pintype "passive"))
      (node (ref "Q70") (pin "3") (pinfunction "OUT_3") (pintype "passive"))
      (node (ref "R27") (pin "2") (pinfunction "2_2") (pintype "passive"))
    )
    (net (code "12") (name "/D5") (class "Default")
      (node (ref "Q17") (pin "3") (pinfunction "OUT_3") (pintype "passive"))
      (node (ref "Q26") (pin "3") (pinfunction "OUT_3") (pintype "passive"))
      (node (ref "Q35") (pin "3") (pinfunction "OUT_3") (pintype "passive"))
      (node (ref "Q44") (pin "3") (pinfunction "OUT_3") (pintype "passive"))
      (node (ref "Q53") (pin "3") (pinfunction "OUT_3") (pintype "passive"))
      (node (ref "Q6") (pin "3") (pinfunction "OUT_3") (pintype "passive"))
      (node (ref "Q62") (pin "3") (pinfunction "OUT_3") (pintype "passive"))
      (node (ref "Q71") (pin "3") (pinfunction "OUT_3") (pintype "passive"))
      (node (ref "R28") (pin "2") (pinfunction "2_2") (pintype "passive"))
    )
    (net (code "13") (name "/D6") (class "Default")
      (node (ref "Q18") (pin "3") (pinfunction "OUT_3") (pintype "passive"))
      (node (ref "Q27") (pin "3") (pinfunction "OUT_3") (pintype "passive"))
      (node (ref "Q36") (pin "3") (pinfunction "OUT_3") (pintype "passive"))
      (node (ref "Q45") (pin "3") (pinfunction "OUT_3") (pintype "passive"))
      (node (ref "Q54") (pin "3") (pinfunction "OUT_3") (pintype "passive"))
      (node (ref "Q63") (pin "3") (pinfunction "OUT_3") (pintype "passive"))
      (node (ref "Q7") (pin "3") (pinfunction "OUT_3") (pintype "passive"))
      (node (ref "Q72") (pin "3") (pinfunction "OUT_3") (pintype "passive"))
      (node (ref "R29") (pin "2") (pinfunction "2_2") (pintype "passive"))
    )
    (net (code "14") (name "/D7") (class "Default")
      (node (ref "Q19") (pin "3") (pinfunction "OUT_3") (pintype "passive"))
      (node (ref "Q28") (pin "3") (pinfunction "OUT_3") (pintype "passive"))
      (node (ref "Q37") (pin "3") (pinfunction "OUT_3") (pintype "passive"))
      (node (ref "Q46") (pin "3") (pinfunction "OUT_3") (pintype "passive"))
      (node (ref "Q55") (pin "3") (pinfunction "OUT_3") (pintype "passive"))
      (node (ref "Q64") (pin "3") (pinfunction "OUT_3") (pintype "passive"))
      (node (ref "Q73") (pin "3") (pinfunction "OUT_3") (pintype "passive"))
      (node (ref "Q8") (pin "3") (pinfunction "OUT_3") (pintype "passive"))
      (node (ref "R30") (pin "2") (pinfunction "2_2") (pintype "passive"))
    )
    (net (code "15") (name "/DAT_I") (class "Default")
      (node (ref "U2") (pin "9") (pinfunction "Q7_9") (pintype "passive"))
      (node (ref "U3") (pin "11") (pinfunction "SDA/FB/PWM1/P1.4_11") (pintype "passive"))
    )
    (net (code "16") (name "/DAT_O") (class "Default")
      (node (ref "IC1") (pin "14") (pinfunction "DS_14") (pintype "passive"))
      (node (ref "U3") (pin "14") (pinfunction "PWM1/IC1/AIN7/CLO/P1.1_14") (pintype "passive"))
    )
    (net (code "17") (name "/ICP_CLK") (class "Default")
      (node (ref "P2") (pin "4") (pinfunction "CLK_4") (pintype "passive"))
      (node (ref "U3") (pin "18") (pinfunction "P0.2/ICPCLK/RXD_1/[SCL]_18") (pintype "passive"))
    )
    (net (code "18") (name "/ICP_DA") (class "Default")
      (node (ref "P2") (pin "3") (pinfunction "DAT_3") (pintype "passive"))
      (node (ref "U3") (pin "8") (pinfunction "[SDA]/TXD_1/ICPDAT/P1.6_8") (pintype "passive"))
    )
    (net (code "19") (name "/LAT_I") (class "Default")
      (node (ref "U2") (pin "1") (pinfunction "~{PL}_1") (pintype "passive"))
      (node (ref "U3") (pin "10") (pinfunction "PWM5/IC7/~{SS}/P1.5_10") (pintype "passive"))
    )
    (net (code "20") (name "/LAT_O") (class "Default")
      (node (ref "IC1") (pin "12") (pinfunction "STCP_12") (pintype "passive"))
      (node (ref "U3") (pin "13") (pinfunction "PWM0/IC0/P1.2_13") (pintype "passive"))
    )
    (net (code "21") (name "/RST") (class "Default")
      (node (ref "P2") (pin "5") (pinfunction "~{RS}T_5") (pintype "passive"))
      (node (ref "R22") (pin "2") (pinfunction "2_2") (pintype "passive"))
      (node (ref "U3") (pin "4") (pinfunction "~{RST}/P2.0_4") (pintype "passive"))
    )
    (net (code "22") (name "/RX3.3V") (class "Default")
      (node (ref "P1") (pin "2") (pinfunction "2_2") (pintype "passive"))
      (node (ref "Q11") (pin "2") (pinfunction "S_2") (pintype "passive"))
      (node (ref "R6") (pin "1") (pinfunction "1_1") (pintype "passive"))
    )
    (net (code "23") (name "/RX5V") (class "Default")
      (node (ref "Q11") (pin "3") (pinfunction "D_3") (pintype "passive"))
      (node (ref "R3") (pin "1") (pinfunction "1_1") (pintype "passive"))
      (node (ref "U3") (pin "3") (pinfunction "P0.7/RXD/AIN2_3") (pintype "passive"))
    )
    (net (code "24") (name "/T1") (class "Default")
      (node (ref "Q9") (pin "1") (pinfunction "B_1") (pintype "passive"))
      (node (ref "R1") (pin "1") (pinfunction "1_1") (pintype "passive"))
      (node (ref "R10") (pin "1") (pinfunction "1_1") (pintype "passive"))
    )
    (net (code "25") (name "/T2") (class "Default")
      (node (ref "Q20") (pin "1") (pinfunction "B_1") (pintype "passive"))
      (node (ref "R11") (pin "1") (pinfunction "1_1") (pintype "passive"))
      (node (ref "R7") (pin "1") (pinfunction "1_1") (pintype "passive"))
    )
    (net (code "26") (name "/T3") (class "Default")
      (node (ref "Q29") (pin "1") (pinfunction "B_1") (pintype "passive"))
      (node (ref "R12") (pin "1") (pinfunction "1_1") (pintype "passive"))
      (node (ref "R8") (pin "1") (pinfunction "1_1") (pintype "passive"))
    )
    (net (code "27") (name "/T4") (class "Default")
      (node (ref "Q38") (pin "1") (pinfunction "B_1") (pintype "passive"))
      (node (ref "R13") (pin "1") (pinfunction "1_1") (pintype "passive"))
      (node (ref "R9") (pin "1") (pinfunction "1_1") (pintype "passive"))
    )
    (net (code "28") (name "/T5") (class "Default")
      (node (ref "Q47") (pin "1") (pinfunction "B_1") (pintype "passive"))
      (node (ref "R14") (pin "1") (pinfunction "1_1") (pintype "passive"))
      (node (ref "R15") (pin "1") (pinfunction "1_1") (pintype "passive"))
    )
    (net (code "29") (name "/T6") (class "Default")
      (node (ref "Q56") (pin "1") (pinfunction "B_1") (pintype "passive"))
      (node (ref "R16") (pin "1") (pinfunction "1_1") (pintype "passive"))
      (node (ref "R19") (pin "1") (pinfunction "1_1") (pintype "passive"))
    )
    (net (code "30") (name "/T7") (class "Default")
      (node (ref "Q65") (pin "1") (pinfunction "B_1") (pintype "passive"))
      (node (ref "R17") (pin "1") (pinfunction "1_1") (pintype "passive"))
      (node (ref "R20") (pin "1") (pinfunction "1_1") (pintype "passive"))
    )
    (net (code "31") (name "/T8") (class "Default")
      (node (ref "Q74") (pin "1") (pinfunction "B_1") (pintype "passive"))
      (node (ref "R18") (pin "1") (pinfunction "1_1") (pintype "passive"))
      (node (ref "R21") (pin "1") (pinfunction "1_1") (pintype "passive"))
    )
    (net (code "32") (name "/TX3.3V") (class "Default")
      (node (ref "P1") (pin "3") (pinfunction "3_3") (pintype "passive"))
      (node (ref "Q10") (pin "2") (pinfunction "S_2") (pintype "passive"))
      (node (ref "R5") (pin "1") (pinfunction "1_1") (pintype "passive"))
    )
    (net (code "33") (name "/TX5V") (class "Default")
      (node (ref "Q10") (pin "3") (pinfunction "D_3") (pintype "passive"))
      (node (ref "R2") (pin "1") (pinfunction "1_1") (pintype "passive"))
      (node (ref "U3") (pin "2") (pinfunction "P0.6/TXD/AIN3_2") (pintype "passive"))
    )
    (net (code "34") (name "GND") (class "Default")
      (node (ref "C1") (pin "2") (pinfunction "2_2") (pintype "passive"))
      (node (ref "C2") (pin "1") (pinfunction "1_1") (pintype "passive"))
      (node (ref "C3") (pin "2") (pinfunction "2_2") (pintype "passive"))
      (node (ref "C4") (pin "1") (pinfunction "1_1") (pintype "passive"))
      (node (ref "C5") (pin "1") (pinfunction "1_1") (pintype "passive"))
      (node (ref "C6") (pin "1") (pinfunction "1_1") (pintype "passive"))
      (node (ref "C7") (pin "2") (pinfunction "2_2") (pintype "passive"))
      (node (ref "C8") (pin "2") (pinfunction "2_2") (pintype "passive"))
      (node (ref "CN1") (pin "1") (pinfunction "-_1") (pintype "passive"))
      (node (ref "CN1") (pin "3") (pinfunction "3_3") (pintype "passive"))
      (node (ref "CN1") (pin "4") (pinfunction "4_4") (pintype "passive"))
      (node (ref "D3") (pin "1") (pinfunction "A_1") (pintype "passive"))
      (node (ref "IC1") (pin "13") (pinfunction "~{OE}_13") (pintype "passive"))
      (node (ref "IC1") (pin "8") (pinfunction "GND_8") (pintype "power_in"))
      (node (ref "L_PW1") (pin "2") (pinfunction "2_2") (pintype "passive"))
      (node (ref "P1") (pin "1") (pinfunction "1_1") (pintype "passive"))
      (node (ref "P2") (pin "6") (pinfunction "GND_6") (pintype "passive"))
      (node (ref "Q20") (pin "2") (pinfunction "E_2") (pintype "passive"))
      (node (ref "Q29") (pin "2") (pinfunction "E_2") (pintype "passive"))
      (node (ref "Q38") (pin "2") (pinfunction "E_2") (pintype "passive"))
      (node (ref "Q47") (pin "2") (pinfunction "E_2") (pintype "passive"))
      (node (ref "Q56") (pin "2") (pinfunction "E_2") (pintype "passive"))
      (node (ref "Q65") (pin "2") (pinfunction "E_2") (pintype "passive"))
      (node (ref "Q74") (pin "2") (pinfunction "E_2") (pintype "passive"))
      (node (ref "Q9") (pin "2") (pinfunction "E_2") (pintype "passive"))
      (node (ref "R1") (pin "2") (pinfunction "2_2") (pintype "passive"))
      (node (ref "R14") (pin "2") (pinfunction "2_2") (pintype "passive"))
      (node (ref "R19") (pin "2") (pinfunction "2_2") (pintype "passive"))
      (node (ref "R20") (pin "2") (pinfunction "2_2") (pintype "passive"))
      (node (ref "R21") (pin "2") (pinfunction "2_2") (pintype "passive"))
      (node (ref "R7") (pin "2") (pinfunction "2_2") (pintype "passive"))
      (node (ref "R8") (pin "2") (pinfunction "2_2") (pintype "passive"))
      (node (ref "R9") (pin "2") (pinfunction "2_2") (pintype "passive"))
      (node (ref "U1") (pin "3") (pinfunction "GND_3") (pintype "passive"))
      (node (ref "U1") (pin "5") (pinfunction "~{ON}/OFF_5") (pintype "passive"))
      (node (ref "U2") (pin "10") (pinfunction "DS_10") (pintype "passive"))
      (node (ref "U2") (pin "15") (pinfunction "~{CE}_15") (pintype "passive"))
      (node (ref "U2") (pin "8") (pinfunction "GND_8") (pintype "power_in"))
      (node (ref "U3") (pin "7") (pinfunction "GND_7") (pintype "passive"))
    )
    (net (code "35") (name "Net-(D3-K)") (class "Default")
      (node (ref "D3") (pin "2") (pinfunction "K_2") (pintype "passive"))
      (node (ref "L1") (pin "1") (pinfunction "1_1") (pintype "passive"))
      (node (ref "U1") (pin "2") (pinfunction "Vo_2") (pintype "passive"))
    )
    (net (code "36") (name "Net-(IC1-QA)") (class "Default")
      (node (ref "IC1") (pin "15") (pinfunction "QA_15") (pintype "passive"))
      (node (ref "R10") (pin "2") (pinfunction "2_2") (pintype "passive"))
    )
    (net (code "37") (name "Net-(IC1-QB)") (class "Default")
      (node (ref "IC1") (pin "1") (pinfunction "QB_1") (pintype "passive"))
      (node (ref "R11") (pin "2") (pinfunction "2_2") (pintype "passive"))
    )
    (net (code "38") (name "Net-(IC1-QC)") (class "Default")
      (node (ref "IC1") (pin "2") (pinfunction "QC_2") (pintype "passive"))
      (node (ref "R12") (pin "2") (pinfunction "2_2") (pintype "passive"))
    )
    (net (code "39") (name "Net-(IC1-QD)") (class "Default")
      (node (ref "IC1") (pin "3") (pinfunction "QD_3") (pintype "passive"))
      (node (ref "R13") (pin "2") (pinfunction "2_2") (pintype "passive"))
    )
    (net (code "40") (name "Net-(IC1-QE)") (class "Default")
      (node (ref "IC1") (pin "4") (pinfunction "QE_4") (pintype "passive"))
      (node (ref "R15") (pin "2") (pinfunction "2_2") (pintype "passive"))
    )
    (net (code "41") (name "Net-(IC1-QF)") (class "Default")
      (node (ref "IC1") (pin "5") (pinfunction "QF_5") (pintype "passive"))
      (node (ref "R16") (pin "2") (pinfunction "2_2") (pintype "passive"))
    )
    (net (code "42") (name "Net-(IC1-QG)") (class "Default")
      (node (ref "IC1") (pin "6") (pinfunction "QG_6") (pintype "passive"))
      (node (ref "R17") (pin "2") (pinfunction "2_2") (pintype "passive"))
    )
    (net (code "43") (name "Net-(IC1-QH)") (class "Default")
      (node (ref "IC1") (pin "7") (pinfunction "QH_7") (pintype "passive"))
      (node (ref "R18") (pin "2") (pinfunction "2_2") (pintype "passive"))
    )
    (net (code "44") (name "Net-(L_PW1-Pad1)") (class "Default")
      (node (ref "L_PW1") (pin "1") (pinfunction "1_1") (pintype "passive"))
      (node (ref "R4") (pin "2") (pinfunction "2_2") (pintype "passive"))
    )
    (net (code "45") (name "Net-(Q1-GND)") (class "Default")
      (node (ref "D1") (pin "2") (pinfunction "2_2") (pintype "passive"))
      (node (ref "Q1") (pin "2") (pinfunction "GND_2") (pintype "passive"))
      (node (ref "Q2") (pin "2") (pinfunction "GND_2") (pintype "passive"))
      (node (ref "Q3") (pin "2") (pinfunction "GND_2") (pintype "passive"))
      (node (ref "Q4") (pin "2") (pinfunction "GND_2") (pintype "passive"))
      (node (ref "Q5") (pin "2") (pinfunction "GND_2") (pintype "passive"))
      (node (ref "Q6") (pin "2") (pinfunction "GND_2") (pintype "passive"))
      (node (ref "Q7") (pin "2") (pinfunction "GND_2") (pintype "passive"))
      (node (ref "Q8") (pin "2") (pinfunction "GND_2") (pintype "passive"))
      (node (ref "Q9") (pin "3") (pinfunction "C_3") (pintype "passive"))
    )
    (net (code "46") (name "Net-(Q12-GND)") (class "Default")
      (node (ref "D4") (pin "2") (pinfunction "2_2") (pintype "passive"))
      (node (ref "Q12") (pin "2") (pinfunction "GND_2") (pintype "passive"))
      (node (ref "Q13") (pin "2") (pinfunction "GND_2") (pintype "passive"))
      (node (ref "Q14") (pin "2") (pinfunction "GND_2") (pintype "passive"))
      (node (ref "Q15") (pin "2") (pinfunction "GND_2") (pintype "passive"))
      (node (ref "Q16") (pin "2") (pinfunction "GND_2") (pintype "passive"))
      (node (ref "Q17") (pin "2") (pinfunction "GND_2") (pintype "passive"))
      (node (ref "Q18") (pin "2") (pinfunction "GND_2") (pintype "passive"))
      (node (ref "Q19") (pin "2") (pinfunction "GND_2") (pintype "passive"))
      (node (ref "Q20") (pin "3") (pinfunction "C_3") (pintype "passive"))
    )
    (net (code "47") (name "Net-(Q21-GND)") (class "Default")
      (node (ref "D5") (pin "2") (pinfunction "2_2") (pintype "passive"))
      (node (ref "Q21") (pin "2") (pinfunction "GND_2") (pintype "passive"))
      (node (ref "Q22") (pin "2") (pinfunction "GND_2") (pintype "passive"))
      (node (ref "Q23") (pin "2") (pinfunction "GND_2") (pintype "passive"))
      (node (ref "Q24") (pin "2") (pinfunction "GND_2") (pintype "passive"))
      (node (ref "Q25") (pin "2") (pinfunction "GND_2") (pintype "passive"))
      (node (ref "Q26") (pin "2") (pinfunction "GND_2") (pintype "passive"))
      (node (ref "Q27") (pin "2") (pinfunction "GND_2") (pintype "passive"))
      (node (ref "Q28") (pin "2") (pinfunction "GND_2") (pintype "passive"))
      (node (ref "Q29") (pin "3") (pinfunction "C_3") (pintype "passive"))
    )
    (net (code "48") (name "Net-(Q30-GND)") (class "Default")
      (node (ref "D6") (pin "2") (pinfunction "2_2") (pintype "passive"))
      (node (ref "Q30") (pin "2") (pinfunction "GND_2") (pintype "passive"))
      (node (ref "Q31") (pin "2") (pinfunction "GND_2") (pintype "passive"))
      (node (ref "Q32") (pin "2") (pinfunction "GND_2") (pintype "passive"))
      (node (ref "Q33") (pin "2") (pinfunction "GND_2") (pintype "passive"))
      (node (ref "Q34") (pin "2") (pinfunction "GND_2") (pintype "passive"))
      (node (ref "Q35") (pin "2") (pinfunction "GND_2") (pintype "passive"))
      (node (ref "Q36") (pin "2") (pinfunction "GND_2") (pintype "passive"))
      (node (ref "Q37") (pin "2") (pinfunction "GND_2") (pintype "passive"))
      (node (ref "Q38") (pin "3") (pinfunction "C_3") (pintype "passive"))
    )
    (net (code "49") (name "Net-(Q39-GND)") (class "Default")
      (node (ref "D7") (pin "2") (pinfunction "2_2") (pintype "passive"))
      (node (ref "Q39") (pin "2") (pinfunction "GND_2") (pintype "passive"))
      (node (ref "Q40") (pin "2") (pinfunction "GND_2") (pintype "passive"))
      (node (ref "Q41") (pin "2") (pinfunction "GND_2") (pintype "passive"))
      (node (ref "Q42") (pin "2") (pinfunction "GND_2") (pintype "passive"))
      (node (ref "Q43") (pin "2") (pinfunction "GND_2") (pintype "passive"))
      (node (ref "Q44") (pin "2") (pinfunction "GND_2") (pintype "passive"))
      (node (ref "Q45") (pin "2") (pinfunction "GND_2") (pintype "passive"))
      (node (ref "Q46") (pin "2") (pinfunction "GND_2") (pintype "passive"))
      (node (ref "Q47") (pin "3") (pinfunction "C_3") (pintype "passive"))
    )
    (net (code "50") (name "Net-(Q48-GND)") (class "Default")
      (node (ref "D8") (pin "2") (pinfunction "2_2") (pintype "passive"))
      (node (ref "Q48") (pin "2") (pinfunction "GND_2") (pintype "passive"))
      (node (ref "Q49") (pin "2") (pinfunction "GND_2") (pintype "passive"))
      (node (ref "Q50") (pin "2") (pinfunction "GND_2") (pintype "passive"))
      (node (ref "Q51") (pin "2") (pinfunction "GND_2") (pintype "passive"))
      (node (ref "Q52") (pin "2") (pinfunction "GND_2") (pintype "passive"))
      (node (ref "Q53") (pin "2") (pinfunction "GND_2") (pintype "passive"))
      (node (ref "Q54") (pin "2") (pinfunction "GND_2") (pintype "passive"))
      (node (ref "Q55") (pin "2") (pinfunction "GND_2") (pintype "passive"))
      (node (ref "Q56") (pin "3") (pinfunction "C_3") (pintype "passive"))
    )
    (net (code "51") (name "Net-(Q57-GND)") (class "Default")
      (node (ref "D9") (pin "2") (pinfunction "2_2") (pintype "passive"))
      (node (ref "Q57") (pin "2") (pinfunction "GND_2") (pintype "passive"))
      (node (ref "Q58") (pin "2") (pinfunction "GND_2") (pintype "passive"))
      (node (ref "Q59") (pin "2") (pinfunction "GND_2") (pintype "passive"))
      (node (ref "Q60") (pin "2") (pinfunction "GND_2") (pintype "passive"))
      (node (ref "Q61") (pin "2") (pinfunction "GND_2") (pintype "passive"))
      (node (ref "Q62") (pin "2") (pinfunction "GND_2") (pintype "passive"))
      (node (ref "Q63") (pin "2") (pinfunction "GND_2") (pintype "passive"))
      (node (ref "Q64") (pin "2") (pinfunction "GND_2") (pintype "passive"))
      (node (ref "Q65") (pin "3") (pinfunction "C_3") (pintype "passive"))
    )
    (net (code "52") (name "Net-(Q66-GND)") (class "Default")
      (node (ref "D10") (pin "2") (pinfunction "2_2") (pintype "passive"))
      (node (ref "Q66") (pin "2") (pinfunction "GND_2") (pintype "passive"))
      (node (ref "Q67") (pin "2") (pinfunction "GND_2") (pintype "passive"))
      (node (ref "Q68") (pin "2") (pinfunction "GND_2") (pintype "passive"))
      (node (ref "Q69") (pin "2") (pinfunction "GND_2") (pintype "passive"))
      (node (ref "Q70") (pin "2") (pinfunction "GND_2") (pintype "passive"))
      (node (ref "Q71") (pin "2") (pinfunction "GND_2") (pintype "passive"))
      (node (ref "Q72") (pin "2") (pinfunction "GND_2") (pintype "passive"))
      (node (ref "Q73") (pin "2") (pinfunction "GND_2") (pintype "passive"))
      (node (ref "Q74") (pin "3") (pinfunction "C_3") (pintype "passive"))
    )
    (net (code "53") (name "Net-(U2-D0)") (class "Default")
      (node (ref "R23") (pin "1") (pinfunction "1_1") (pintype "passive"))
      (node (ref "U2") (pin "11") (pinfunction "D0_11") (pintype "passive"))
    )
    (net (code "54") (name "Net-(U2-D1)") (class "Default")
      (node (ref "R24") (pin "1") (pinfunction "1_1") (pintype "passive"))
      (node (ref "U2") (pin "12") (pinfunction "D1_12") (pintype "passive"))
    )
    (net (code "55") (name "Net-(U2-D2)") (class "Default")
      (node (ref "R25") (pin "1") (pinfunction "1_1") (pintype "passive"))
      (node (ref "U2") (pin "13") (pinfunction "D2_13") (pintype "passive"))
    )
    (net (code "56") (name "Net-(U2-D3)") (class "Default")
      (node (ref "R26") (pin "1") (pinfunction "1_1") (pintype "passive"))
      (node (ref "U2") (pin "14") (pinfunction "D3_14") (pintype "passive"))
    )
    (net (code "57") (name "Net-(U2-D4)") (class "Default")
      (node (ref "R27") (pin "1") (pinfunction "1_1") (pintype "passive"))
      (node (ref "U2") (pin "3") (pinfunction "D4_3") (pintype "passive"))
    )
    (net (code "58") (name "Net-(U2-D5)") (class "Default")
      (node (ref "R28") (pin "1") (pinfunction "1_1") (pintype "passive"))
      (node (ref "U2") (pin "4") (pinfunction "D5_4") (pintype "passive"))
    )
    (net (code "59") (name "Net-(U2-D6)") (class "Default")
      (node (ref "R29") (pin "1") (pinfunction "1_1") (pintype "passive"))
      (node (ref "U2") (pin "5") (pinfunction "D6_5") (pintype "passive"))
    )
    (net (code "60") (name "Net-(U2-D7)") (class "Default")
      (node (ref "R30") (pin "1") (pinfunction "1_1") (pintype "passive"))
      (node (ref "U2") (pin "6") (pinfunction "D7_6") (pintype "passive"))
    )
    (net (code "61") (name "unconnected-(IC1-QH'-Pad9)") (class "Default")
      (node (ref "IC1") (pin "9") (pinfunction "QH'_9") (pintype "passive"))
    )
    (net (code "62") (name "unconnected-(Q21-OUT-Pad3)") (class "Default")
      (node (ref "Q21") (pin "3") (pinfunction "OUT_3") (pintype "passive"))
    )
    (net (code "63") (name "unconnected-(U2-~{Q7}-Pad7)") (class "Default")
      (node (ref "U2") (pin "7") (pinfunction "~{Q7}_7") (pintype "passive"))
    )
    (net (code "64") (name "unconnected-(U3-AIN0{slash}~{INT1}{slash}P1.7-Pad6)") (class "Default")
      (node (ref "U3") (pin "6") (pinfunction "AIN0/~{INT1}/P1.7_6") (pintype "passive"))
    )
    (net (code "65") (name "unconnected-(U3-P0.0{slash}PWM3{slash}IC3{slash}MOSI{slash}T1-Pad16)") (class "Default")
      (node (ref "U3") (pin "16") (pinfunction "P0.0/PWM3/IC3/MOSI/T1_16") (pintype "passive"))
    )
    (net (code "66") (name "unconnected-(U3-P0.1{slash}PWM4{slash}IC4{slash}MISO-Pad17)") (class "Default")
      (node (ref "U3") (pin "17") (pinfunction "P0.1/PWM4/IC4/MISO_17") (pintype "passive"))
    )
    (net (code "67") (name "unconnected-(U3-P0.3{slash}PWM5{slash}IC5{slash}AIN6-Pad19)") (class "Default")
      (node (ref "U3") (pin "19") (pinfunction "P0.3/PWM5/IC5/AIN6_19") (pintype "passive"))
    )
    (net (code "68") (name "unconnected-(U3-P0.4{slash}AIN5{slash}STADC{slash}PWM3{slash}IC3-Pad20)") (class "Default")
      (node (ref "U3") (pin "20") (pinfunction "P0.4/AIN5/STADC/PWM3/IC3_20") (pintype "passive"))
    )
    (net (code "69") (name "unconnected-(U3-P0.5{slash}PWM2{slash}IC6{slash}T0{slash}AIN4-Pad1)") (class "Default")
      (node (ref "U3") (pin "1") (pinfunction "P0.5/PWM2/IC6/T0/AIN4_1") (pintype "passive"))
    )
    (net (code "70") (name "unconnected-(U3-~{INT0}{slash}OSCIN{slash}AIN1{slash}P3.0-Pad5)") (class "Default")
      (node (ref "U3") (pin "5") (pinfunction "~{INT0}/OSCIN/AIN1/P3.0_5") (pintype "passive"))
    )
  )
)
